# TX_custom.net
KiCad netlist of a schematic drawn in Altium Designer
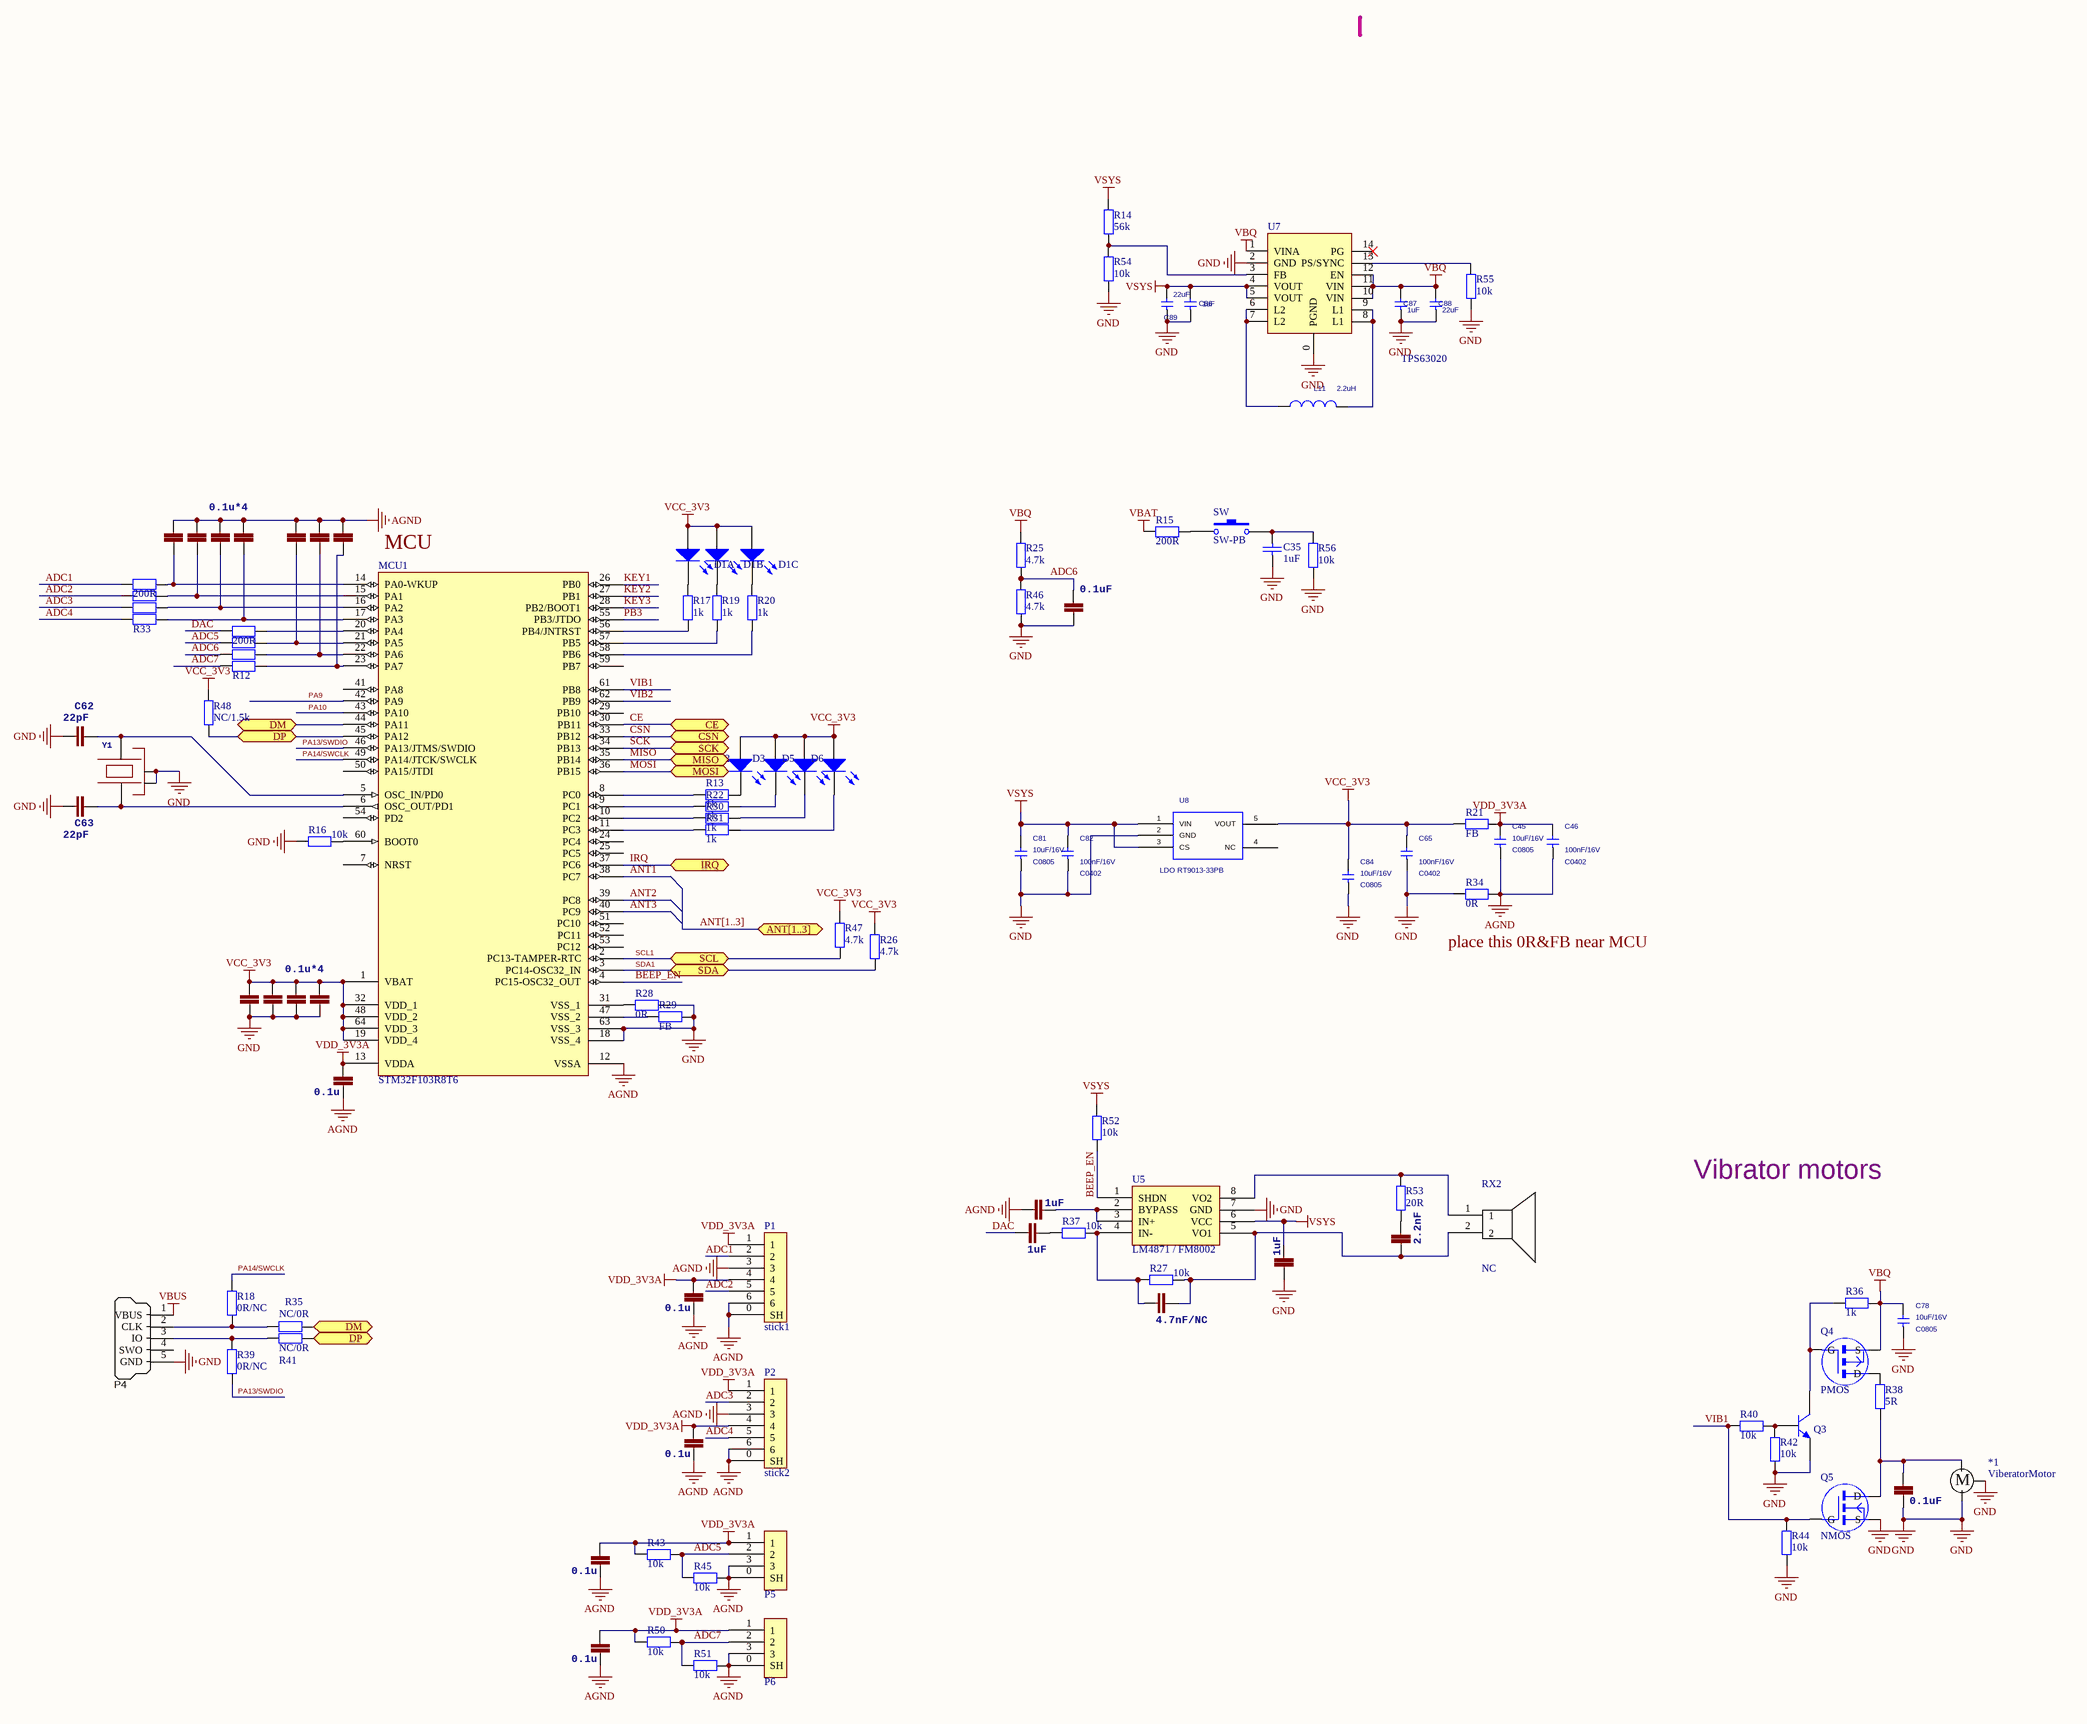
[diagram p0: TX_custom.SchDoc]

(export (version "E")
  (design (tool "Eeschema 10.0.6"))
  (components
    (comp (ref "*1")
      (value "ViberatorMotor")
      (footprint "VibratorMotor")
      (libsource (lib "sch") (part "ViberatorMotor"))
    )
    (comp (ref "C35")
      (value "1uF")
      (footprint "0402")
      (description "Capacitor")
      (fields (field (name "PUBLISHER") "Altium Limited"))
      (libsource (lib "RTC6705") (part "Cap"))
    )
    (comp (ref "C37")
      (value "0.1uF")
      (footprint "0603")
      (description "<b>Capacitor</b>\nStandard 0603 ceramic capacitor, and 0.1\" leaded capacitor.")
      (fields (field (name "PARTNO") "CC0402ZRY5V7BB104"))
      (libsource (lib "") (part "CAP0402-CAP_1"))
    )
    (comp (ref "C45")
      (value "10uF/16V")
      (footprint "0805")
      (fields (field (name "PCB DECAL") "C0805") (field (name "Comment") "C"))
      (libsource (lib "*") (part "C"))
    )
    (comp (ref "C46")
      (value "100nF/16V")
      (footprint "0603")
      (fields (field (name "PCB DECAL") "C0402") (field (name "Comment") "C"))
      (libsource (lib "*") (part "C"))
    )
    (comp (ref "C54")
      (value "0.1u*4")
      (footprint "0402")
      (description "<b>Capacitor</b>\nStandard 0603 ceramic capacitor, and 0.1\" leaded capacitor.")
      (fields (field (name "PARTNO") "CC0402ZRY5V7BB104"))
      (libsource (lib "pixhawk2") (part "CAP0402-CAP"))
    )
    (comp (ref "C55")
      (value "1n")
      (footprint "0402")
      (description "<b>Capacitor</b>\nStandard 0603 ceramic capacitor, and 0.1\" leaded capacitor.")
      (fields (field (name "PARTNO") "CC0402ZRY5V7BB104"))
      (libsource (lib "pixhawk2") (part "CAP0402-CAP"))
    )
    (comp (ref "C56")
      (value "1n")
      (footprint "0402")
      (description "<b>Capacitor</b>\nStandard 0603 ceramic capacitor, and 0.1\" leaded capacitor.")
      (fields (field (name "PARTNO") "CC0402ZRY5V7BB104"))
      (libsource (lib "pixhawk2") (part "CAP0402-CAP"))
    )
    (comp (ref "C57")
      (value "1n")
      (footprint "0402")
      (description "<b>Capacitor</b>\nStandard 0603 ceramic capacitor, and 0.1\" leaded capacitor.")
      (fields (field (name "PARTNO") "CC0402ZRY5V7BB104"))
      (libsource (lib "pixhawk2") (part "CAP0402-CAP"))
    )
    (comp (ref "C58")
      (value "1n")
      (footprint "0402")
      (description "<b>Capacitor</b>\nStandard 0603 ceramic capacitor, and 0.1\" leaded capacitor.")
      (fields (field (name "PARTNO") "CC0402ZRY5V7BB104"))
      (libsource (lib "pixhawk2") (part "CAP0402-CAP"))
    )
    (comp (ref "C59")
      (value "1n")
      (footprint "0402")
      (description "<b>Capacitor</b>\nStandard 0603 ceramic capacitor, and 0.1\" leaded capacitor.")
      (fields (field (name "PARTNO") "CC0402ZRY5V7BB104"))
      (libsource (lib "pixhawk2") (part "CAP0402-CAP"))
    )
    (comp (ref "C60")
      (value "1n")
      (footprint "0402")
      (description "<b>Capacitor</b>\nStandard 0603 ceramic capacitor, and 0.1\" leaded capacitor.")
      (fields (field (name "PARTNO") "CC0402ZRY5V7BB104"))
      (libsource (lib "pixhawk2") (part "CAP0402-CAP"))
    )
    (comp (ref "C61")
      (value "0.1uF")
      (footprint "0402")
      (description "<b>Capacitor</b>\nStandard 0603 ceramic capacitor, and 0.1\" leaded capacitor.")
      (fields (field (name "PARTNO") "CC0402ZRY5V7BB104"))
      (libsource (lib "pixhawk2") (part "CAP0402-CAP"))
    )
    (comp (ref "C62")
      (value "22pF")
      (footprint "0402")
      (description "<b>Capacitor</b>\nStandard 0603 ceramic capacitor, and 0.1\" leaded capacitor.")
      (fields (field (name "PARTNO") "CC0402ZRY5V7BB104"))
      (libsource (lib "") (part "CAP0402-CAP_2"))
    )
    (comp (ref "C63")
      (value "22pF")
      (footprint "0402")
      (description "<b>Capacitor</b>\nStandard 0603 ceramic capacitor, and 0.1\" leaded capacitor.")
      (fields (field (name "PARTNO") "CC0402ZRY5V7BB104"))
      (libsource (lib "*") (part "CAP0402-CAP"))
    )
    (comp (ref "C65")
      (value "100nF/16V")
      (footprint "0603")
      (fields (field (name "PCB DECAL") "C0402") (field (name "Comment") "C"))
      (libsource (lib "*") (part "C"))
    )
    (comp (ref "C67")
      (value "0.1u*4")
      (footprint "0402")
      (description "<b>Capacitor</b>\nStandard 0603 ceramic capacitor, and 0.1\" leaded capacitor.")
      (fields (field (name "PARTNO") "CC0402ZRY5V7BB104"))
      (libsource (lib "pixhawk2") (part "CAP0402-CAP"))
    )
    (comp (ref "C68")
      (value "1n")
      (footprint "0402")
      (description "<b>Capacitor</b>\nStandard 0603 ceramic capacitor, and 0.1\" leaded capacitor.")
      (fields (field (name "PARTNO") "CC0402ZRY5V7BB104"))
      (libsource (lib "pixhawk2") (part "CAP0402-CAP"))
    )
    (comp (ref "C69")
      (value "1n")
      (footprint "0402")
      (description "<b>Capacitor</b>\nStandard 0603 ceramic capacitor, and 0.1\" leaded capacitor.")
      (fields (field (name "PARTNO") "CC0402ZRY5V7BB104"))
      (libsource (lib "pixhawk2") (part "CAP0402-CAP"))
    )
    (comp (ref "C70")
      (value "1n")
      (footprint "0402")
      (description "<b>Capacitor</b>\nStandard 0603 ceramic capacitor, and 0.1\" leaded capacitor.")
      (fields (field (name "PARTNO") "CC0402ZRY5V7BB104"))
      (libsource (lib "pixhawk2") (part "CAP0402-CAP"))
    )
    (comp (ref "C71")
      (value "0.1u")
      (footprint "0402")
      (description "<b>Capacitor</b>\nStandard 0603 ceramic capacitor, and 0.1\" leaded capacitor.")
      (fields (field (name "PARTNO") "CC0402ZRY5V7BB104"))
      (libsource (lib "pixhawk2") (part "CAP0402-CAP"))
    )
    (comp (ref "C72")
      (value "1uF")
      (footprint "0603")
      (description "<b>Capacitor</b>\nStandard 0603 ceramic capacitor, and 0.1\" leaded capacitor.")
      (fields (field (name "PARTNO") "CC0402ZRY5V7BB104"))
      (libsource (lib "") (part "CAP0402-CAP_2"))
    )
    (comp (ref "C73")
      (value "1uF")
      (footprint "0603")
      (description "<b>Capacitor</b>\nStandard 0603 ceramic capacitor, and 0.1\" leaded capacitor.")
      (fields (field (name "PARTNO") "CC0402ZRY5V7BB104"))
      (libsource (lib "") (part "CAP0402-CAP_2"))
    )
    (comp (ref "C74")
      (value "2.2nF")
      (footprint "0402")
      (description "<b>Capacitor</b>\nStandard 0603 ceramic capacitor, and 0.1\" leaded capacitor.")
      (fields (field (name "PARTNO") "CC0402ZRY5V7BB104"))
      (libsource (lib "") (part "CAP0402-CAP_1"))
    )
    (comp (ref "C75")
      (value "1uF")
      (footprint "0603")
      (description "<b>Capacitor</b>\nStandard 0603 ceramic capacitor, and 0.1\" leaded capacitor.")
      (fields (field (name "PARTNO") "CC0402ZRY5V7BB104"))
      (libsource (lib "") (part "CAP0402-CAP_1"))
    )
    (comp (ref "C76")
      (value "4.7nF/NC")
      (footprint "0402")
      (description "<b>Capacitor</b>\nStandard 0603 ceramic capacitor, and 0.1\" leaded capacitor.")
      (fields (field (name "PARTNO") "CC0402ZRY5V7BB104"))
      (libsource (lib "") (part "CAP0402-CAP_2"))
    )
    (comp (ref "C77")
      (value "0.1u")
      (footprint "0402")
      (description "<b>Capacitor</b>\nStandard 0603 ceramic capacitor, and 0.1\" leaded capacitor.")
      (fields (field (name "PARTNO") "CC0402ZRY5V7BB104"))
      (libsource (lib "pixhawk2") (part "CAP0402-CAP"))
    )
    (comp (ref "C78")
      (value "10uF/16V")
      (footprint "0805")
      (fields (field (name "PCB DECAL") "C0805") (field (name "Comment") "C"))
      (libsource (lib "*") (part "C"))
    )
    (comp (ref "C79")
      (value "0.1u")
      (footprint "0402")
      (description "<b>Capacitor</b>\nStandard 0603 ceramic capacitor, and 0.1\" leaded capacitor.")
      (fields (field (name "PARTNO") "CC0402ZRY5V7BB104"))
      (libsource (lib "pixhawk2") (part "CAP0402-CAP"))
    )
    (comp (ref "C80")
      (value "0.1u")
      (footprint "0402")
      (description "<b>Capacitor</b>\nStandard 0603 ceramic capacitor, and 0.1\" leaded capacitor.")
      (fields (field (name "PARTNO") "CC0402ZRY5V7BB104"))
      (libsource (lib "pixhawk2") (part "CAP0402-CAP"))
    )
    (comp (ref "C81")
      (value "10uF/16V")
      (footprint "0805")
      (fields (field (name "PCB DECAL") "C0805") (field (name "Comment") "C"))
      (libsource (lib "*") (part "C"))
    )
    (comp (ref "C82")
      (value "100nF/16V")
      (footprint "0603")
      (fields (field (name "PCB DECAL") "C0402") (field (name "Comment") "C"))
      (libsource (lib "*") (part "C"))
    )
    (comp (ref "C83")
      (value "0.1u")
      (footprint "0402")
      (description "<b>Capacitor</b>\nStandard 0603 ceramic capacitor, and 0.1\" leaded capacitor.")
      (fields (field (name "PARTNO") "CC0402ZRY5V7BB104"))
      (libsource (lib "pixhawk2") (part "CAP0402-CAP"))
    )
    (comp (ref "C84")
      (value "10uF/16V")
      (footprint "0805")
      (fields (field (name "PCB DECAL") "C0805") (field (name "Comment") "C"))
      (libsource (lib "*") (part "C"))
    )
    (comp (ref "C86") (value "1uF") (footprint "0805") (libsource (lib "*") (part "C")))
    (comp (ref "C87") (value "1uF") (footprint "0805") (libsource (lib "*") (part "C")))
    (comp (ref "C88") (value "22uF") (footprint "0805") (libsource (lib "*") (part "C")))
    (comp (ref "C89") (value "22uF") (footprint "0805") (libsource (lib "*") (part "C")))
    (comp (ref "D1")
      (value "LEDx3")
      (footprint "LC-0603_Rx2")
      (description "Typical RED GaAs LED")
      (fields (field (name "PUBLISHER") "Altium Limited"))
      (libsource (lib "sch") (part "LEDx3"))
    )
    (comp (ref "D2")
      (value "LED0")
      (footprint "0603LED")
      (description "Typical INFRARED GaAs LED")
      (fields (field (name "PUBLISHER") "Altium Limited"))
      (libsource (lib "Miscellaneous Devices") (part "LED0"))
    )
    (comp (ref "D3")
      (value "LED0")
      (footprint "0603LED")
      (description "Typical INFRARED GaAs LED")
      (fields (field (name "PUBLISHER") "Altium Limited"))
      (libsource (lib "Miscellaneous Devices") (part "LED0"))
    )
    (comp (ref "D5")
      (value "LED0")
      (footprint "0603LED")
      (description "Typical INFRARED GaAs LED")
      (fields (field (name "PUBLISHER") "Altium Limited"))
      (libsource (lib "Miscellaneous Devices") (part "LED0"))
    )
    (comp (ref "D6")
      (value "LED0")
      (footprint "0603LED")
      (description "Typical INFRARED GaAs LED")
      (fields (field (name "PUBLISHER") "Altium Limited"))
      (libsource (lib "Miscellaneous Devices") (part "LED0"))
    )
    (comp (ref "L11") (value "2.2uH") (footprint "L3015") (libsource (lib "*") (part "INDUCTOR")))
    (comp (ref "MCU1")
      (value "STM32F103R8T6")
      (footprint "LQFP64_N")
      (description "STM32 ARM-based 32-bit MCU with 64 Kbytes Flash, 64-pin LQFP, Industrial Temperature")
      (fields (field (name "PUBLISHER") "*"))
      (libsource (lib "ST Microcontroller 32-Bit STM32 SCH") (part "STM32F103R8T6"))
    )
    (comp (ref "P1") (value "stick1") (footprint "WFRSM125 - 6P") (libsource (lib "sch") (part "6PSocket_T")))
    (comp (ref "P2") (value "stick2") (footprint "WFRSM125 - 6P") (libsource (lib "sch") (part "6PSocket_T")))
    (comp (ref "P4")
      (value "SWD_MicroUSB")
      (footprint "MICRO-YZX")
      (description "Connector SMD USB Micro Type B middle mount")
      (libsource (lib "sch") (part "SWD_MicroUSB"))
    )
    (comp (ref "P5")
      (value "3PSocket_T")
      (footprint "WFRSM125 - 3P")
      (libsource (lib "sch") (part "3PSocket_T"))
    )
    (comp (ref "P6")
      (value "3PSocket_T")
      (footprint "WFRSM125 - 3P")
      (libsource (lib "sch") (part "3PSocket_T"))
    )
    (comp (ref "Q3")
      (value "NPN")
      (footprint "SOT-23B_L")
      (description "NPN Bipolar Transistor")
      (fields (field (name "PUBLISHER") "Altium Limited"))
      (libsource (lib "sch") (part "NPN"))
    )
    (comp (ref "Q4") (value "PMOS") (footprint "SOT-23B_L") (libsource (lib "sch") (part "PMOS")))
    (comp (ref "Q5") (value "NMOS") (footprint "SOT-23B_L") (libsource (lib "sch") (part "NMOS")))
    (comp (ref "R12")
      (value "200R")
      (footprint "0402X4")
      (description "Resistor")
      (fields (field (name "PUBLISHER") "Altium Limited"))
      (libsource (lib "sch") (part "Res*4"))
    )
    (comp (ref "R13")
      (value "1k")
      (footprint "0402")
      (description "Resistor")
      (fields (field (name "PUBLISHER") "Altium Limited"))
      (libsource (lib "") (part "Res2_1"))
    )
    (comp (ref "R14")
      (value "56k")
      (footprint "0402")
      (description "Resistor")
      (fields (field (name "PUBLISHER") "Altium Limited"))
      (libsource (lib "") (part "Res2_1"))
    )
    (comp (ref "R15")
      (value "200R")
      (footprint "0402")
      (description "Resistor")
      (fields (field (name "PUBLISHER") "Altium Limited"))
      (libsource (lib "") (part "Res2_3"))
    )
    (comp (ref "R16")
      (value "10k")
      (footprint "0402")
      (description "Resistor")
      (fields (field (name "PUBLISHER") "Altium Limited"))
      (libsource (lib "") (part "Res2_2"))
    )
    (comp (ref "R17")
      (value "1k")
      (footprint "0402")
      (description "Resistor")
      (fields (field (name "PUBLISHER") "Altium Limited"))
      (libsource (lib "") (part "Res2_3"))
    )
    (comp (ref "R18")
      (value "0R/NC")
      (footprint "0402")
      (description "Resistor")
      (fields (field (name "PUBLISHER") "Altium Limited"))
      (libsource (lib "Miscellaneous Devices") (part "Res2"))
    )
    (comp (ref "R19")
      (value "1k")
      (footprint "0402")
      (description "Resistor")
      (fields (field (name "PUBLISHER") "Altium Limited"))
      (libsource (lib "") (part "Res2_3"))
    )
    (comp (ref "R20")
      (value "1k")
      (footprint "0402")
      (description "Resistor")
      (fields (field (name "PUBLISHER") "Altium Limited"))
      (libsource (lib "") (part "Res2_3"))
    )
    (comp (ref "R21")
      (value "FB")
      (footprint "0402")
      (description "Resistor")
      (fields (field (name "PUBLISHER") "Altium Limited"))
      (libsource (lib "") (part "Res2_2"))
    )
    (comp (ref "R22")
      (value "1k")
      (footprint "0402")
      (description "Resistor")
      (fields (field (name "PUBLISHER") "Altium Limited"))
      (libsource (lib "") (part "Res2_1"))
    )
    (comp (ref "R25")
      (value "4.7k")
      (footprint "0402")
      (description "Resistor")
      (fields (field (name "PUBLISHER") "Altium Limited"))
      (libsource (lib "RTC6705") (part "Res2"))
    )
    (comp (ref "R26")
      (value "4.7k")
      (footprint "0402")
      (description "Resistor")
      (fields (field (name "PUBLISHER") "Altium Limited"))
      (libsource (lib "RTC6705") (part "Res2"))
    )
    (comp (ref "R27")
      (value "10k")
      (footprint "0402")
      (description "Resistor")
      (fields (field (name "PUBLISHER") "Altium Limited"))
      (libsource (lib "") (part "Res2_2"))
    )
    (comp (ref "R28")
      (value "0R")
      (footprint "0402")
      (description "Resistor")
      (fields (field (name "PUBLISHER") "Altium Limited"))
      (libsource (lib "") (part "Res2_2"))
    )
    (comp (ref "R29")
      (value "FB")
      (footprint "0402")
      (description "Resistor")
      (fields (field (name "PUBLISHER") "Altium Limited"))
      (libsource (lib "") (part "Res2_2"))
    )
    (comp (ref "R30")
      (value "1k")
      (footprint "0402")
      (description "Resistor")
      (fields (field (name "PUBLISHER") "Altium Limited"))
      (libsource (lib "") (part "Res2_1"))
    )
    (comp (ref "R31")
      (value "1k")
      (footprint "0402")
      (description "Resistor")
      (fields (field (name "PUBLISHER") "Altium Limited"))
      (libsource (lib "") (part "Res2_1"))
    )
    (comp (ref "R33")
      (value "200R")
      (footprint "0402X4")
      (description "Resistor")
      (fields (field (name "PUBLISHER") "Altium Limited"))
      (libsource (lib "sch") (part "Res*4"))
    )
    (comp (ref "R34")
      (value "0R")
      (footprint "0402")
      (description "Resistor")
      (fields (field (name "PUBLISHER") "Altium Limited"))
      (libsource (lib "") (part "Res2_2"))
    )
    (comp (ref "R35")
      (value "NC/0R")
      (footprint "0402")
      (description "Resistor")
      (fields (field (name "PUBLISHER") "Altium Limited"))
      (libsource (lib "") (part "Res2_1"))
    )
    (comp (ref "R36")
      (value "1k")
      (footprint "0402")
      (description "Resistor")
      (fields (field (name "PUBLISHER") "Altium Limited"))
      (libsource (lib "") (part "Res2_2"))
    )
    (comp (ref "R37")
      (value "10k")
      (footprint "0402")
      (description "Resistor")
      (fields (field (name "PUBLISHER") "Altium Limited"))
      (libsource (lib "") (part "Res2_2"))
    )
    (comp (ref "R38")
      (value "5R")
      (footprint "0603")
      (description "Resistor")
      (fields (field (name "PUBLISHER") "Altium Limited"))
      (libsource (lib "RTC6705") (part "Res2"))
    )
    (comp (ref "R39")
      (value "0R/NC")
      (footprint "0402")
      (description "Resistor")
      (fields (field (name "PUBLISHER") "Altium Limited"))
      (libsource (lib "Miscellaneous Devices") (part "Res2"))
    )
    (comp (ref "R40")
      (value "10k")
      (footprint "0402")
      (description "Resistor")
      (fields (field (name "PUBLISHER") "Altium Limited"))
      (libsource (lib "") (part "Res2_2"))
    )
    (comp (ref "R41")
      (value "NC/0R")
      (footprint "0402")
      (description "Resistor")
      (fields (field (name "PUBLISHER") "Altium Limited"))
      (libsource (lib "") (part "Res2_1"))
    )
    (comp (ref "R42")
      (value "10k")
      (footprint "0402")
      (description "Resistor")
      (fields (field (name "PUBLISHER") "Altium Limited"))
      (libsource (lib "RTC6705") (part "Res2"))
    )
    (comp (ref "R43")
      (value "10k")
      (footprint "0402")
      (description "Resistor")
      (fields (field (name "PUBLISHER") "Altium Limited"))
      (libsource (lib "") (part "Res2_2"))
    )
    (comp (ref "R44")
      (value "10k")
      (footprint "0402")
      (description "Resistor")
      (fields (field (name "PUBLISHER") "Altium Limited"))
      (libsource (lib "RTC6705") (part "Res2"))
    )
    (comp (ref "R45")
      (value "10k")
      (footprint "0402")
      (description "Resistor")
      (fields (field (name "PUBLISHER") "Altium Limited"))
      (libsource (lib "") (part "Res2_2"))
    )
    (comp (ref "R46")
      (value "4.7k")
      (footprint "0402")
      (description "Resistor")
      (fields (field (name "PUBLISHER") "Altium Limited"))
      (libsource (lib "RTC6705") (part "Res2"))
    )
    (comp (ref "R47")
      (value "4.7k")
      (footprint "0402")
      (description "Resistor")
      (fields (field (name "PUBLISHER") "Altium Limited"))
      (libsource (lib "RTC6705") (part "Res2"))
    )
    (comp (ref "R48")
      (value "NC/1.5k")
      (footprint "0402")
      (description "Resistor")
      (fields (field (name "PUBLISHER") "Altium Limited"))
      (libsource (lib "RTC6705") (part "Res2"))
    )
    (comp (ref "R50")
      (value "10k")
      (footprint "0402")
      (description "Resistor")
      (fields (field (name "PUBLISHER") "Altium Limited"))
      (libsource (lib "") (part "Res2_2"))
    )
    (comp (ref "R51")
      (value "10k")
      (footprint "0402")
      (description "Resistor")
      (fields (field (name "PUBLISHER") "Altium Limited"))
      (libsource (lib "") (part "Res2_2"))
    )
    (comp (ref "R52")
      (value "10k")
      (footprint "0402")
      (description "Resistor")
      (fields (field (name "PUBLISHER") "Altium Limited"))
      (libsource (lib "") (part "Res2_3"))
    )
    (comp (ref "R53")
      (value "20R")
      (footprint "0402")
      (description "Resistor")
      (fields (field (name "PUBLISHER") "Altium Limited"))
      (libsource (lib "") (part "Res2_3"))
    )
    (comp (ref "R54")
      (value "10k")
      (footprint "0402")
      (description "Resistor")
      (fields (field (name "PUBLISHER") "Altium Limited"))
      (libsource (lib "") (part "Res2_1"))
    )
    (comp (ref "R55")
      (value "10k")
      (footprint "0402")
      (description "Resistor")
      (fields (field (name "PUBLISHER") "Altium Limited"))
      (libsource (lib "") (part "Res2_1"))
    )
    (comp (ref "R56")
      (value "10k")
      (footprint "0402")
      (description "Resistor")
      (fields (field (name "PUBLISHER") "Altium Limited"))
      (libsource (lib "RTC6705") (part "Res2"))
    )
    (comp (ref "RX2") (value "NC") (footprint "sonar-10mm") (libsource (lib "schlib") (part "sonar")))
    (comp (ref "SW")
      (value "SW-PB")
      (footprint "SW3x4")
      (description "Switch")
      (fields (field (name "PUBLISHER") "Altium Limited"))
      (libsource (lib "Miscellaneous Devices") (part "SW-PB"))
    )
    (comp (ref "U5")
      (value "LM4871 / FM8002")
      (footprint "SOIC8_39MM")
      (libsource (lib "sch") (part "LM4871"))
    )
    (comp (ref "U7") (value "TPS63020") (footprint "TPS63020") (libsource (lib "sch") (part "TPS63020")))
    (comp (ref "U8")
      (value "LDO RT9013-33PB")
      (footprint "SOT23-5")
      (fields (field (name "Comment") "RT9193-33_1_2"))
      (libsource (lib "*") (part "RT9193-33_1_2"))
    )
    (comp (ref "Y1")
      (value "16Mhz")
      (footprint "OSCILLATOR-3.2X2.5")
      (description "Crystal Oscillator in 3.2x2.5 SMD")
      (libsource (lib "pixhawk2") (part "OSCILLATOR-3.2X2.5"))
    )
  )
  (nets
    (net (code "1") (name "/ADC1") (class "Default")
      (node (ref "P1") (pin "2") (pinfunction "2_2") (pintype "passive"))
      (node (ref "R33") (pin "1") (pinfunction "1_1") (pintype "passive"))
    )
    (net (code "2") (name "/ADC2") (class "Default")
      (node (ref "P1") (pin "5") (pinfunction "5_5") (pintype "passive"))
      (node (ref "R33") (pin "2") (pinfunction "2_2") (pintype "passive"))
    )
    (net (code "3") (name "/ADC3") (class "Default")
      (node (ref "P2") (pin "2") (pinfunction "2_2") (pintype "passive"))
      (node (ref "R33") (pin "3") (pinfunction "3_3") (pintype "passive"))
    )
    (net (code "4") (name "/ADC4") (class "Default")
      (node (ref "P2") (pin "5") (pinfunction "5_5") (pintype "passive"))
      (node (ref "R33") (pin "4") (pinfunction "4_4") (pintype "passive"))
    )
    (net (code "5") (name "/ADC5") (class "Default")
      (node (ref "P5") (pin "2") (pinfunction "2_2") (pintype "passive"))
      (node (ref "R12") (pin "2") (pinfunction "2_2") (pintype "passive"))
      (node (ref "R43") (pin "2") (pinfunction "2_2") (pintype "passive"))
      (node (ref "R45") (pin "1") (pinfunction "1_1") (pintype "passive"))
    )
    (net (code "6") (name "/ADC6") (class "Default")
      (node (ref "C61") (pin "2") (pinfunction "2_2") (pintype "passive"))
      (node (ref "R12") (pin "3") (pinfunction "3_3") (pintype "passive"))
      (node (ref "R25") (pin "1") (pinfunction "1_1") (pintype "passive"))
      (node (ref "R46") (pin "2") (pinfunction "2_2") (pintype "passive"))
    )
    (net (code "7") (name "/ADC7") (class "Default")
      (node (ref "P6") (pin "2") (pinfunction "2_2") (pintype "passive"))
      (node (ref "R12") (pin "4") (pinfunction "4_4") (pintype "passive"))
      (node (ref "R50") (pin "2") (pinfunction "2_2") (pintype "passive"))
      (node (ref "R51") (pin "1") (pinfunction "1_1") (pintype "passive"))
    )
    (net (code "8") (name "/ANT1") (class "Default")
      (node (ref "MCU1") (pin "38") (pinfunction "PC7_38") (pintype "bidirectional"))
    )
    (net (code "9") (name "/ANT2") (class "Default")
      (node (ref "MCU1") (pin "39") (pinfunction "PC8_39") (pintype "bidirectional"))
    )
    (net (code "10") (name "/ANT3") (class "Default")
      (node (ref "MCU1") (pin "40") (pinfunction "PC9_40") (pintype "bidirectional"))
    )
    (net (code "12") (name "/BEEP_EN") (class "Default")
      (node (ref "MCU1") (pin "4") (pinfunction "PC15-OSC32_OUT_4") (pintype "bidirectional"))
      (node (ref "R52") (pin "1") (pinfunction "1_1") (pintype "passive"))
      (node (ref "U5") (pin "1") (pinfunction "SHDN_1") (pintype "passive"))
    )
    (net (code "13") (name "/CE") (class "Default")
      (node (ref "MCU1") (pin "30") (pinfunction "PB11_30") (pintype "bidirectional"))
    )
    (net (code "14") (name "/CSN") (class "Default")
      (node (ref "MCU1") (pin "33") (pinfunction "PB12_33") (pintype "bidirectional"))
    )
    (net (code "15") (name "/DAC") (class "Default")
      (node (ref "C73") (pin "2") (pinfunction "2_2") (pintype "passive"))
      (node (ref "R12") (pin "1") (pinfunction "1_1") (pintype "passive"))
    )
    (net (code "16") (name "/DM") (class "Default")
      (node (ref "MCU1") (pin "44") (pinfunction "PA11_44") (pintype "bidirectional"))
      (node (ref "R35") (pin "1") (pinfunction "1_1") (pintype "passive"))
    )
    (net (code "17") (name "/DP") (class "Default")
      (node (ref "MCU1") (pin "45") (pinfunction "PA12_45") (pintype "bidirectional"))
      (node (ref "R41") (pin "1") (pinfunction "1_1") (pintype "passive"))
      (node (ref "R48") (pin "1") (pinfunction "1_1") (pintype "passive"))
    )
    (net (code "18") (name "/IRQ") (class "Default")
      (node (ref "MCU1") (pin "37") (pinfunction "PC6_37") (pintype "bidirectional"))
    )
    (net (code "19") (name "/KEY1") (class "Default")
      (node (ref "MCU1") (pin "26") (pinfunction "PB0_26") (pintype "bidirectional"))
    )
    (net (code "20") (name "/KEY2") (class "Default")
      (node (ref "MCU1") (pin "27") (pinfunction "PB1_27") (pintype "bidirectional"))
    )
    (net (code "21") (name "/KEY3") (class "Default")
      (node (ref "MCU1") (pin "28") (pinfunction "PB2/BOOT1_28") (pintype "bidirectional"))
    )
    (net (code "22") (name "/MISO") (class "Default")
      (node (ref "MCU1") (pin "35") (pinfunction "PB14_35") (pintype "bidirectional"))
    )
    (net (code "23") (name "/MOSI") (class "Default")
      (node (ref "MCU1") (pin "36") (pinfunction "PB15_36") (pintype "bidirectional"))
    )
    (net (code "24") (name "/PA9") (class "Default")
      (node (ref "MCU1") (pin "42") (pinfunction "PA9_42") (pintype "bidirectional"))
    )
    (net (code "25") (name "/PA10") (class "Default")
      (node (ref "MCU1") (pin "43") (pinfunction "PA10_43") (pintype "bidirectional"))
    )
    (net (code "26") (name "/PA13{slash}SWDIO") (class "Default")
      (node (ref "MCU1") (pin "46") (pinfunction "PA13/JTMS/SWDIO_46") (pintype "bidirectional"))
      (node (ref "R39") (pin "2") (pinfunction "2_2") (pintype "passive"))
    )
    (net (code "27") (name "/PA14{slash}SWCLK") (class "Default")
      (node (ref "MCU1") (pin "49") (pinfunction "PA14/JTCK/SWCLK_49") (pintype "bidirectional"))
      (node (ref "R18") (pin "1") (pinfunction "1_1") (pintype "passive"))
    )
    (net (code "28") (name "/PB3") (class "Default")
      (node (ref "MCU1") (pin "55") (pinfunction "PB3/JTDO_55") (pintype "bidirectional"))
    )
    (net (code "29") (name "/SCK") (class "Default")
      (node (ref "MCU1") (pin "34") (pinfunction "PB13_34") (pintype "bidirectional"))
    )
    (net (code "30") (name "/SCL1") (class "Default")
      (node (ref "MCU1") (pin "2") (pinfunction "PC13-TAMPER-RTC_2") (pintype "bidirectional"))
      (node (ref "R47") (pin "1") (pinfunction "1_1") (pintype "passive"))
    )
    (net (code "31") (name "/SDA1") (class "Default")
      (node (ref "MCU1") (pin "3") (pinfunction "PC14-OSC32_IN_3") (pintype "bidirectional"))
      (node (ref "R26") (pin "1") (pinfunction "1_1") (pintype "passive"))
    )
    (net (code "32") (name "/VIB1") (class "Default")
      (node (ref "MCU1") (pin "61") (pinfunction "PB8_61") (pintype "bidirectional"))
      (node (ref "Q5") (pin "G") (pinfunction "G_G") (pintype "passive"))
      (node (ref "R40") (pin "2") (pinfunction "2_2") (pintype "passive"))
      (node (ref "R44") (pin "2") (pinfunction "2_2") (pintype "passive"))
    )
    (net (code "33") (name "/VIB2") (class "Default")
      (node (ref "MCU1") (pin "62") (pinfunction "PB9_62") (pintype "bidirectional"))
    )
    (net (code "34") (name "AGND") (class "Default")
      (node (ref "C45") (pin "2") (pinfunction "2_2") (pintype "passive"))
      (node (ref "C46") (pin "2") (pinfunction "2_2") (pintype "passive"))
      (node (ref "C54") (pin "2") (pinfunction "2_2") (pintype "passive"))
      (node (ref "C55") (pin "2") (pinfunction "2_2") (pintype "passive"))
      (node (ref "C56") (pin "2") (pinfunction "2_2") (pintype "passive"))
      (node (ref "C57") (pin "2") (pinfunction "2_2") (pintype "passive"))
      (node (ref "C58") (pin "2") (pinfunction "2_2") (pintype "passive"))
      (node (ref "C59") (pin "2") (pinfunction "2_2") (pintype "passive"))
      (node (ref "C60") (pin "2") (pinfunction "2_2") (pintype "passive"))
      (node (ref "C71") (pin "1") (pinfunction "1_1") (pintype "passive"))
      (node (ref "C72") (pin "2") (pinfunction "2_2") (pintype "passive"))
      (node (ref "C77") (pin "1") (pinfunction "1_1") (pintype "passive"))
      (node (ref "C79") (pin "1") (pinfunction "1_1") (pintype "passive"))
      (node (ref "C80") (pin "1") (pinfunction "1_1") (pintype "passive"))
      (node (ref "C83") (pin "1") (pinfunction "1_1") (pintype "passive"))
      (node (ref "MCU1") (pin "12") (pinfunction "VSSA_12") (pintype "power_in"))
      (node (ref "P1") (pin "0") (pinfunction "SH_0") (pintype "passive"))
      (node (ref "P1") (pin "3") (pinfunction "3_3") (pintype "passive"))
      (node (ref "P1") (pin "6") (pinfunction "6_6") (pintype "passive"))
      (node (ref "P2") (pin "0") (pinfunction "SH_0") (pintype "passive"))
      (node (ref "P2") (pin "3") (pinfunction "3_3") (pintype "passive"))
      (node (ref "P2") (pin "6") (pinfunction "6_6") (pintype "passive"))
      (node (ref "P5") (pin "0") (pinfunction "SH_0") (pintype "passive"))
      (node (ref "P5") (pin "3") (pinfunction "3_3") (pintype "passive"))
      (node (ref "P6") (pin "0") (pinfunction "SH_0") (pintype "passive"))
      (node (ref "P6") (pin "3") (pinfunction "3_3") (pintype "passive"))
      (node (ref "R34") (pin "1") (pinfunction "1_1") (pintype "passive"))
      (node (ref "R45") (pin "2") (pinfunction "2_2") (pintype "passive"))
      (node (ref "R51") (pin "2") (pinfunction "2_2") (pintype "passive"))
    )
    (net (code "35") (name "GND") (class "Default")
      (node (ref "*1") (pin "0") (pinfunction "0_0") (pintype "passive"))
      (node (ref "*1") (pin "2") (pinfunction "2_2") (pintype "passive"))
      (node (ref "C35") (pin "2") (pinfunction "2_2") (pintype "passive"))
      (node (ref "C37") (pin "2") (pinfunction "2_2") (pintype "passive"))
      (node (ref "C61") (pin "1") (pinfunction "1_1") (pintype "passive"))
      (node (ref "C62") (pin "2") (pinfunction "2_2") (pintype "passive"))
      (node (ref "C63") (pin "2") (pinfunction "2_2") (pintype "passive"))
      (node (ref "C65") (pin "2") (pinfunction "2_2") (pintype "passive"))
      (node (ref "C67") (pin "1") (pinfunction "1_1") (pintype "passive"))
      (node (ref "C68") (pin "1") (pinfunction "1_1") (pintype "passive"))
      (node (ref "C69") (pin "1") (pinfunction "1_1") (pintype "passive"))
      (node (ref "C70") (pin "1") (pinfunction "1_1") (pintype "passive"))
      (node (ref "C75") (pin "2") (pinfunction "2_2") (pintype "passive"))
      (node (ref "C78") (pin "2") (pinfunction "2_2") (pintype "passive"))
      (node (ref "C81") (pin "2") (pinfunction "2_2") (pintype "passive"))
      (node (ref "C82") (pin "2") (pinfunction "2_2") (pintype "passive"))
      (node (ref "C84") (pin "2") (pinfunction "2_2") (pintype "passive"))
      (node (ref "C86") (pin "2") (pinfunction "2_2") (pintype "passive"))
      (node (ref "C87") (pin "2") (pinfunction "2_2") (pintype "passive"))
      (node (ref "C88") (pin "2") (pinfunction "2_2") (pintype "passive"))
      (node (ref "C89") (pin "2") (pinfunction "2_2") (pintype "passive"))
      (node (ref "MCU1") (pin "18") (pinfunction "VSS_4_18") (pintype "power_in"))
      (node (ref "MCU1") (pin "63") (pinfunction "VSS_3_63") (pintype "power_in"))
      (node (ref "P4") (pin "5") (pinfunction "GND_5") (pintype "passive"))
      (node (ref "Q3") (pin "2") (pinfunction "E_2") (pintype "passive"))
      (node (ref "Q5") (pin "S") (pinfunction "S_S") (pintype "passive"))
      (node (ref "R16") (pin "1") (pinfunction "1_1") (pintype "passive"))
      (node (ref "R28") (pin "1") (pinfunction "1_1") (pintype "passive"))
      (node (ref "R29") (pin "1") (pinfunction "1_1") (pintype "passive"))
      (node (ref "R34") (pin "2") (pinfunction "2_2") (pintype "passive"))
      (node (ref "R42") (pin "1") (pinfunction "1_1") (pintype "passive"))
      (node (ref "R44") (pin "1") (pinfunction "1_1") (pintype "passive"))
      (node (ref "R46") (pin "1") (pinfunction "1_1") (pintype "passive"))
      (node (ref "R54") (pin "2") (pinfunction "2_2") (pintype "passive"))
      (node (ref "R55") (pin "2") (pinfunction "2_2") (pintype "passive"))
      (node (ref "R56") (pin "1") (pinfunction "1_1") (pintype "passive"))
      (node (ref "U5") (pin "7") (pinfunction "GND_7") (pintype "passive"))
      (node (ref "U7") (pin "0") (pinfunction "PGND_0") (pintype "passive"))
      (node (ref "U7") (pin "2") (pinfunction "GND_2") (pintype "passive"))
      (node (ref "U8") (pin "2") (pinfunction "GND_2") (pintype "passive"))
      (node (ref "Y1") (pin "2") (pinfunction "NC_2_2") (pintype "open_emitter"))
      (node (ref "Y1") (pin "4") (pinfunction "NC_4_4") (pintype "open_emitter"))
    )
    (net (code "36") (name "Net-(*1-Pad1)") (class "Default")
      (node (ref "*1") (pin "1") (pinfunction "1_1") (pintype "passive"))
      (node (ref "C37") (pin "1") (pinfunction "1_1") (pintype "passive"))
      (node (ref "Q5") (pin "D") (pinfunction "D_D") (pintype "passive"))
      (node (ref "R38") (pin "1") (pinfunction "1_1") (pintype "passive"))
    )
    (net (code "37") (name "Net-(C35-Pad1)") (class "Default")
      (node (ref "C35") (pin "1") (pinfunction "1_1") (pintype "passive"))
      (node (ref "R56") (pin "2") (pinfunction "2_2") (pintype "passive"))
      (node (ref "SW") (pin "2") (pinfunction "2_2") (pintype "passive"))
    )
    (net (code "38") (name "Net-(C73-Pad1)") (class "Default")
      (node (ref "C73") (pin "1") (pinfunction "1_1") (pintype "passive"))
      (node (ref "R37") (pin "1") (pinfunction "1_1") (pintype "passive"))
    )
    (net (code "39") (name "Net-(C74-Pad1)") (class "Default")
      (node (ref "C74") (pin "1") (pinfunction "1_1") (pintype "passive"))
      (node (ref "R53") (pin "1") (pinfunction "1_1") (pintype "passive"))
    )
    (net (code "40") (name "Net-(D1A-K)") (class "Default")
      (node (ref "D1") (pin "2") (pinfunction "K_2") (pintype "passive"))
      (node (ref "R17") (pin "2") (pinfunction "2_2") (pintype "passive"))
    )
    (net (code "41") (name "Net-(D1B-K)") (class "Default")
      (node (ref "D1") (pin "3") (pinfunction "K_3") (pintype "passive"))
      (node (ref "R19") (pin "2") (pinfunction "2_2") (pintype "passive"))
    )
    (net (code "42") (name "Net-(D1C-K)") (class "Default")
      (node (ref "D1") (pin "4") (pinfunction "K_4") (pintype "passive"))
      (node (ref "R20") (pin "2") (pinfunction "2_2") (pintype "passive"))
    )
    (net (code "43") (name "Net-(D2-K)") (class "Default")
      (node (ref "D2") (pin "2") (pinfunction "K_2") (pintype "passive"))
      (node (ref "R13") (pin "1") (pinfunction "1_1") (pintype "passive"))
    )
    (net (code "44") (name "Net-(D3-K)") (class "Default")
      (node (ref "D3") (pin "2") (pinfunction "K_2") (pintype "passive"))
      (node (ref "R22") (pin "1") (pinfunction "1_1") (pintype "passive"))
    )
    (net (code "45") (name "Net-(D5-K)") (class "Default")
      (node (ref "D5") (pin "2") (pinfunction "K_2") (pintype "passive"))
      (node (ref "R30") (pin "1") (pinfunction "1_1") (pintype "passive"))
    )
    (net (code "46") (name "Net-(D6-K)") (class "Default")
      (node (ref "D6") (pin "2") (pinfunction "K_2") (pintype "passive"))
      (node (ref "R31") (pin "1") (pinfunction "1_1") (pintype "passive"))
    )
    (net (code "47") (name "Net-(L11-Pad1)") (class "Default")
      (node (ref "L11") (pin "1") (pinfunction "1_1") (pintype "passive"))
      (node (ref "U7") (pin "8") (pinfunction "L1_8") (pintype "passive"))
      (node (ref "U7") (pin "9") (pinfunction "L1_9") (pintype "passive"))
    )
    (net (code "48") (name "Net-(L11-Pad2)") (class "Default")
      (node (ref "L11") (pin "2") (pinfunction "2_2") (pintype "passive"))
      (node (ref "U7") (pin "6") (pinfunction "L2_6") (pintype "passive"))
      (node (ref "U7") (pin "7") (pinfunction "L2_7") (pintype "passive"))
    )
    (net (code "49") (name "Net-(MCU1-BOOT0)") (class "Default")
      (node (ref "MCU1") (pin "60") (pinfunction "BOOT0_60") (pintype "input"))
      (node (ref "R16") (pin "2") (pinfunction "2_2") (pintype "passive"))
    )
    (net (code "50") (name "Net-(MCU1-OSC_IN{slash}PD0)") (class "Default")
      (node (ref "C62") (pin "1") (pinfunction "1_1") (pintype "passive"))
      (node (ref "MCU1") (pin "5") (pinfunction "OSC_IN/PD0_5") (pintype "input"))
      (node (ref "Y1") (pin "3") (pinfunction "3_3") (pintype "passive"))
    )
    (net (code "51") (name "Net-(MCU1-OSC_OUT{slash}PD1)") (class "Default")
      (node (ref "C63") (pin "1") (pinfunction "1_1") (pintype "passive"))
      (node (ref "MCU1") (pin "6") (pinfunction "OSC_OUT/PD1_6") (pintype "output"))
      (node (ref "Y1") (pin "1") (pinfunction "1_1") (pintype "passive"))
    )
    (net (code "52") (name "Net-(MCU1-PA0-WKUP)") (class "Default")
      (node (ref "C54") (pin "1") (pinfunction "1_1") (pintype "passive"))
      (node (ref "MCU1") (pin "14") (pinfunction "PA0-WKUP_14") (pintype "bidirectional"))
      (node (ref "R33") (pin "8") (pinfunction "8_8") (pintype "passive"))
    )
    (net (code "53") (name "Net-(MCU1-PA1)") (class "Default")
      (node (ref "C55") (pin "1") (pinfunction "1_1") (pintype "passive"))
      (node (ref "MCU1") (pin "15") (pinfunction "PA1_15") (pintype "bidirectional"))
      (node (ref "R33") (pin "7") (pinfunction "7_7") (pintype "passive"))
    )
    (net (code "54") (name "Net-(MCU1-PA2)") (class "Default")
      (node (ref "C56") (pin "1") (pinfunction "1_1") (pintype "passive"))
      (node (ref "MCU1") (pin "16") (pinfunction "PA2_16") (pintype "bidirectional"))
      (node (ref "R33") (pin "6") (pinfunction "6_6") (pintype "passive"))
    )
    (net (code "55") (name "Net-(MCU1-PA3)") (class "Default")
      (node (ref "C57") (pin "1") (pinfunction "1_1") (pintype "passive"))
      (node (ref "MCU1") (pin "17") (pinfunction "PA3_17") (pintype "bidirectional"))
      (node (ref "R33") (pin "5") (pinfunction "5_5") (pintype "passive"))
    )
    (net (code "56") (name "Net-(MCU1-PA4)") (class "Default")
      (node (ref "MCU1") (pin "20") (pinfunction "PA4_20") (pintype "bidirectional"))
      (node (ref "R12") (pin "8") (pinfunction "8_8") (pintype "passive"))
    )
    (net (code "57") (name "Net-(MCU1-PA5)") (class "Default")
      (node (ref "C58") (pin "1") (pinfunction "1_1") (pintype "passive"))
      (node (ref "MCU1") (pin "21") (pinfunction "PA5_21") (pintype "bidirectional"))
      (node (ref "R12") (pin "7") (pinfunction "7_7") (pintype "passive"))
    )
    (net (code "58") (name "Net-(MCU1-PA6)") (class "Default")
      (node (ref "C59") (pin "1") (pinfunction "1_1") (pintype "passive"))
      (node (ref "MCU1") (pin "22") (pinfunction "PA6_22") (pintype "bidirectional"))
      (node (ref "R12") (pin "6") (pinfunction "6_6") (pintype "passive"))
    )
    (net (code "59") (name "Net-(MCU1-PA7)") (class "Default")
      (node (ref "C60") (pin "1") (pinfunction "1_1") (pintype "passive"))
      (node (ref "MCU1") (pin "23") (pinfunction "PA7_23") (pintype "bidirectional"))
      (node (ref "R12") (pin "5") (pinfunction "5_5") (pintype "passive"))
    )
    (net (code "60") (name "Net-(MCU1-PB4{slash}JNTRST)") (class "Default")
      (node (ref "MCU1") (pin "56") (pinfunction "PB4/JNTRST_56") (pintype "bidirectional"))
      (node (ref "R17") (pin "1") (pinfunction "1_1") (pintype "passive"))
    )
    (net (code "61") (name "Net-(MCU1-PB5)") (class "Default")
      (node (ref "MCU1") (pin "57") (pinfunction "PB5_57") (pintype "bidirectional"))
      (node (ref "R19") (pin "1") (pinfunction "1_1") (pintype "passive"))
    )
    (net (code "62") (name "Net-(MCU1-PB6)") (class "Default")
      (node (ref "MCU1") (pin "58") (pinfunction "PB6_58") (pintype "bidirectional"))
      (node (ref "R20") (pin "1") (pinfunction "1_1") (pintype "passive"))
    )
    (net (code "63") (name "Net-(MCU1-PC0)") (class "Default")
      (node (ref "MCU1") (pin "8") (pinfunction "PC0_8") (pintype "bidirectional"))
      (node (ref "R13") (pin "2") (pinfunction "2_2") (pintype "passive"))
    )
    (net (code "64") (name "Net-(MCU1-PC1)") (class "Default")
      (node (ref "MCU1") (pin "9") (pinfunction "PC1_9") (pintype "bidirectional"))
      (node (ref "R22") (pin "2") (pinfunction "2_2") (pintype "passive"))
    )
    (net (code "65") (name "Net-(MCU1-PC2)") (class "Default")
      (node (ref "MCU1") (pin "10") (pinfunction "PC2_10") (pintype "bidirectional"))
      (node (ref "R30") (pin "2") (pinfunction "2_2") (pintype "passive"))
    )
    (net (code "66") (name "Net-(MCU1-PC3)") (class "Default")
      (node (ref "MCU1") (pin "11") (pinfunction "PC3_11") (pintype "bidirectional"))
      (node (ref "R31") (pin "2") (pinfunction "2_2") (pintype "passive"))
    )
    (net (code "67") (name "Net-(MCU1-VSS_1)") (class "Default")
      (node (ref "MCU1") (pin "31") (pinfunction "VSS_1_31") (pintype "power_in"))
      (node (ref "R28") (pin "2") (pinfunction "2_2") (pintype "passive"))
    )
    (net (code "68") (name "Net-(MCU1-VSS_2)") (class "Default")
      (node (ref "MCU1") (pin "47") (pinfunction "VSS_2_47") (pintype "power_in"))
      (node (ref "R29") (pin "2") (pinfunction "2_2") (pintype "passive"))
    )
    (net (code "69") (name "Net-(P4-CLK)") (class "Default")
      (node (ref "P4") (pin "2") (pinfunction "CLK_2") (pintype "passive"))
      (node (ref "R18") (pin "2") (pinfunction "2_2") (pintype "passive"))
      (node (ref "R35") (pin "2") (pinfunction "2_2") (pintype "passive"))
    )
    (net (code "70") (name "Net-(P4-IO)") (class "Default")
      (node (ref "P4") (pin "3") (pinfunction "IO_3") (pintype "passive"))
      (node (ref "R39") (pin "1") (pinfunction "1_1") (pintype "passive"))
      (node (ref "R41") (pin "2") (pinfunction "2_2") (pintype "passive"))
    )
    (net (code "71") (name "Net-(Q3-B)") (class "Default")
      (node (ref "Q3") (pin "1") (pinfunction "B_1") (pintype "passive"))
      (node (ref "R40") (pin "1") (pinfunction "1_1") (pintype "passive"))
      (node (ref "R42") (pin "2") (pinfunction "2_2") (pintype "passive"))
    )
    (net (code "72") (name "Net-(Q3-C)") (class "Default")
      (node (ref "Q3") (pin "3") (pinfunction "C_3") (pintype "passive"))
      (node (ref "Q4") (pin "G") (pinfunction "G_G") (pintype "passive"))
      (node (ref "R36") (pin "2") (pinfunction "2_2") (pintype "passive"))
    )
    (net (code "73") (name "Net-(Q4-PadD)") (class "Default")
      (node (ref "Q4") (pin "D") (pinfunction "D_D") (pintype "passive"))
      (node (ref "R38") (pin "2") (pinfunction "2_2") (pintype "passive"))
    )
    (net (code "74") (name "Net-(R15-Pad2)") (class "Default")
      (node (ref "R15") (pin "2") (pinfunction "2_2") (pintype "passive"))
      (node (ref "SW") (pin "1") (pinfunction "1_1") (pintype "passive"))
    )
    (net (code "75") (name "Net-(U5-BYPASS)") (class "Default")
      (node (ref "C72") (pin "1") (pinfunction "1_1") (pintype "passive"))
      (node (ref "U5") (pin "2") (pinfunction "BYPASS_2") (pintype "passive"))
      (node (ref "U5") (pin "3") (pinfunction "IN+_3") (pintype "passive"))
    )
    (net (code "76") (name "Net-(U5-IN-)") (class "Default")
      (node (ref "C76") (pin "2") (pinfunction "2_2") (pintype "passive"))
      (node (ref "R27") (pin "1") (pinfunction "1_1") (pintype "passive"))
      (node (ref "R37") (pin "2") (pinfunction "2_2") (pintype "passive"))
      (node (ref "U5") (pin "4") (pinfunction "IN-_4") (pintype "passive"))
    )
    (net (code "77") (name "Net-(U5-VO1)") (class "Default")
      (node (ref "C74") (pin "2") (pinfunction "2_2") (pintype "passive"))
      (node (ref "C76") (pin "1") (pinfunction "1_1") (pintype "passive"))
      (node (ref "R27") (pin "2") (pinfunction "2_2") (pintype "passive"))
      (node (ref "RX2") (pin "2") (pinfunction "2_2") (pintype "passive"))
      (node (ref "U5") (pin "5") (pinfunction "VO1_5") (pintype "passive"))
    )
    (net (code "78") (name "Net-(U5-VO2)") (class "Default")
      (node (ref "R53") (pin "2") (pinfunction "2_2") (pintype "passive"))
      (node (ref "RX2") (pin "1") (pinfunction "1_1") (pintype "passive"))
      (node (ref "U5") (pin "8") (pinfunction "VO2_8") (pintype "passive"))
    )
    (net (code "79") (name "Net-(U7-FB)") (class "Default")
      (node (ref "R14") (pin "2") (pinfunction "2_2") (pintype "passive"))
      (node (ref "R54") (pin "1") (pinfunction "1_1") (pintype "passive"))
      (node (ref "U7") (pin "3") (pinfunction "FB_3") (pintype "passive"))
    )
    (net (code "80") (name "Net-(U7-PS{slash}SYNC)") (class "Default")
      (node (ref "R55") (pin "1") (pinfunction "1_1") (pintype "passive"))
      (node (ref "U7") (pin "13") (pinfunction "PS/SYNC_13") (pintype "passive"))
    )
    (net (code "81") (name "VBAT") (class "Default")
      (node (ref "R15") (pin "1") (pinfunction "1_1") (pintype "passive"))
    )
    (net (code "82") (name "VBQ") (class "Default")
      (node (ref "C78") (pin "1") (pinfunction "1_1") (pintype "passive"))
      (node (ref "C87") (pin "1") (pinfunction "1_1") (pintype "passive"))
      (node (ref "C88") (pin "1") (pinfunction "1_1") (pintype "passive"))
      (node (ref "Q4") (pin "S") (pinfunction "S_S") (pintype "passive"))
      (node (ref "R25") (pin "2") (pinfunction "2_2") (pintype "passive"))
      (node (ref "R36") (pin "1") (pinfunction "1_1") (pintype "passive"))
      (node (ref "U7") (pin "1") (pinfunction "VINA_1") (pintype "passive"))
      (node (ref "U7") (pin "10") (pinfunction "VIN_10") (pintype "passive"))
      (node (ref "U7") (pin "11") (pinfunction "VIN_11") (pintype "passive"))
      (node (ref "U7") (pin "12") (pinfunction "EN_12") (pintype "passive"))
    )
    (net (code "83") (name "VBUS") (class "Default")
      (node (ref "P4") (pin "1") (pinfunction "VBUS_1") (pintype "passive"))
    )
    (net (code "84") (name "VCC_3V3") (class "Default")
      (node (ref "C65") (pin "1") (pinfunction "1_1") (pintype "passive"))
      (node (ref "C67") (pin "2") (pinfunction "2_2") (pintype "passive"))
      (node (ref "C68") (pin "2") (pinfunction "2_2") (pintype "passive"))
      (node (ref "C69") (pin "2") (pinfunction "2_2") (pintype "passive"))
      (node (ref "C70") (pin "2") (pinfunction "2_2") (pintype "passive"))
      (node (ref "C84") (pin "1") (pinfunction "1_1") (pintype "passive"))
      (node (ref "D1") (pin "1") (pinfunction "A_1") (pintype "passive"))
      (node (ref "D2") (pin "1") (pinfunction "A_1") (pintype "passive"))
      (node (ref "D3") (pin "1") (pinfunction "A_1") (pintype "passive"))
      (node (ref "D5") (pin "1") (pinfunction "A_1") (pintype "passive"))
      (node (ref "D6") (pin "1") (pinfunction "A_1") (pintype "passive"))
      (node (ref "MCU1") (pin "1") (pinfunction "VBAT_1") (pintype "power_in"))
      (node (ref "MCU1") (pin "19") (pinfunction "VDD_4_19") (pintype "power_in"))
      (node (ref "MCU1") (pin "32") (pinfunction "VDD_1_32") (pintype "power_in"))
      (node (ref "MCU1") (pin "48") (pinfunction "VDD_2_48") (pintype "power_in"))
      (node (ref "MCU1") (pin "64") (pinfunction "VDD_3_64") (pintype "power_in"))
      (node (ref "R21") (pin "2") (pinfunction "2_2") (pintype "passive"))
      (node (ref "R26") (pin "2") (pinfunction "2_2") (pintype "passive"))
      (node (ref "R47") (pin "2") (pinfunction "2_2") (pintype "passive"))
      (node (ref "R48") (pin "2") (pinfunction "2_2") (pintype "passive"))
      (node (ref "U8") (pin "5") (pinfunction "VOUT_5") (pintype "passive"))
    )
    (net (code "85") (name "VDD_3V3A") (class "Default")
      (node (ref "C45") (pin "1") (pinfunction "1_1") (pintype "passive"))
      (node (ref "C46") (pin "1") (pinfunction "1_1") (pintype "passive"))
      (node (ref "C71") (pin "2") (pinfunction "2_2") (pintype "passive"))
      (node (ref "C77") (pin "2") (pinfunction "2_2") (pintype "passive"))
      (node (ref "C79") (pin "2") (pinfunction "2_2") (pintype "passive"))
      (node (ref "C80") (pin "2") (pinfunction "2_2") (pintype "passive"))
      (node (ref "C83") (pin "2") (pinfunction "2_2") (pintype "passive"))
      (node (ref "MCU1") (pin "13") (pinfunction "VDDA_13") (pintype "power_in"))
      (node (ref "P1") (pin "1") (pinfunction "1_1") (pintype "passive"))
      (node (ref "P1") (pin "4") (pinfunction "4_4") (pintype "passive"))
      (node (ref "P2") (pin "1") (pinfunction "1_1") (pintype "passive"))
      (node (ref "P2") (pin "4") (pinfunction "4_4") (pintype "passive"))
      (node (ref "P5") (pin "1") (pinfunction "1_1") (pintype "passive"))
      (node (ref "P6") (pin "1") (pinfunction "1_1") (pintype "passive"))
      (node (ref "R21") (pin "1") (pinfunction "1_1") (pintype "passive"))
      (node (ref "R43") (pin "1") (pinfunction "1_1") (pintype "passive"))
      (node (ref "R50") (pin "1") (pinfunction "1_1") (pintype "passive"))
    )
    (net (code "86") (name "VSYS") (class "Default")
      (node (ref "C75") (pin "1") (pinfunction "1_1") (pintype "passive"))
      (node (ref "C81") (pin "1") (pinfunction "1_1") (pintype "passive"))
      (node (ref "C82") (pin "1") (pinfunction "1_1") (pintype "passive"))
      (node (ref "C86") (pin "1") (pinfunction "1_1") (pintype "passive"))
      (node (ref "C89") (pin "1") (pinfunction "1_1") (pintype "passive"))
      (node (ref "R14") (pin "1") (pinfunction "1_1") (pintype "passive"))
      (node (ref "R52") (pin "2") (pinfunction "2_2") (pintype "passive"))
      (node (ref "U5") (pin "6") (pinfunction "VCC_6") (pintype "passive"))
      (node (ref "U7") (pin "4") (pinfunction "VOUT_4") (pintype "passive"))
      (node (ref "U7") (pin "5") (pinfunction "VOUT_5") (pintype "passive"))
      (node (ref "U8") (pin "1") (pinfunction "VIN_1") (pintype "passive"))
      (node (ref "U8") (pin "3") (pinfunction "CS_3") (pintype "passive"))
    )
    (net (code "87") (name "unconnected-(MCU1-NRST-Pad7)") (class "Default")
      (node (ref "MCU1") (pin "7") (pinfunction "NRST_7") (pintype "bidirectional"))
    )
    (net (code "88") (name "unconnected-(MCU1-PA8-Pad41)") (class "Default")
      (node (ref "MCU1") (pin "41") (pinfunction "PA8_41") (pintype "bidirectional"))
    )
    (net (code "89") (name "unconnected-(MCU1-PA15{slash}JTDI-Pad50)") (class "Default")
      (node (ref "MCU1") (pin "50") (pinfunction "PA15/JTDI_50") (pintype "bidirectional"))
    )
    (net (code "90") (name "unconnected-(MCU1-PB7-Pad59)") (class "Default")
      (node (ref "MCU1") (pin "59") (pinfunction "PB7_59") (pintype "bidirectional"))
    )
    (net (code "91") (name "unconnected-(MCU1-PB10-Pad29)") (class "Default")
      (node (ref "MCU1") (pin "29") (pinfunction "PB10_29") (pintype "bidirectional"))
    )
    (net (code "92") (name "unconnected-(MCU1-PC4-Pad24)") (class "Default")
      (node (ref "MCU1") (pin "24") (pinfunction "PC4_24") (pintype "bidirectional"))
    )
    (net (code "93") (name "unconnected-(MCU1-PC5-Pad25)") (class "Default")
      (node (ref "MCU1") (pin "25") (pinfunction "PC5_25") (pintype "bidirectional"))
    )
    (net (code "94") (name "unconnected-(MCU1-PC10-Pad51)") (class "Default")
      (node (ref "MCU1") (pin "51") (pinfunction "PC10_51") (pintype "bidirectional"))
    )
    (net (code "95") (name "unconnected-(MCU1-PC11-Pad52)") (class "Default")
      (node (ref "MCU1") (pin "52") (pinfunction "PC11_52") (pintype "bidirectional"))
    )
    (net (code "96") (name "unconnected-(MCU1-PC12-Pad53)") (class "Default")
      (node (ref "MCU1") (pin "53") (pinfunction "PC12_53") (pintype "bidirectional"))
    )
    (net (code "97") (name "unconnected-(MCU1-PD2-Pad54)") (class "Default")
      (node (ref "MCU1") (pin "54") (pinfunction "PD2_54") (pintype "bidirectional"))
    )
    (net (code "98") (name "unconnected-(P4-SWO-Pad4)") (class "Default")
      (node (ref "P4") (pin "4") (pinfunction "SWO_4") (pintype "passive"))
    )
    (net (code "99") (name "unconnected-(U7-PG-Pad14)") (class "Default")
      (node (ref "U7") (pin "14") (pinfunction "PG_14") (pintype "passive+no_connect"))
    )
    (net (code "100") (name "unconnected-(U8-NC-Pad4)") (class "Default")
      (node (ref "U8") (pin "4") (pinfunction "NC_4") (pintype "passive"))
    )
  )
)
